# USBINFRTransiever_POWER.net
KiCad netlist of a schematic drawn in Altium Designer
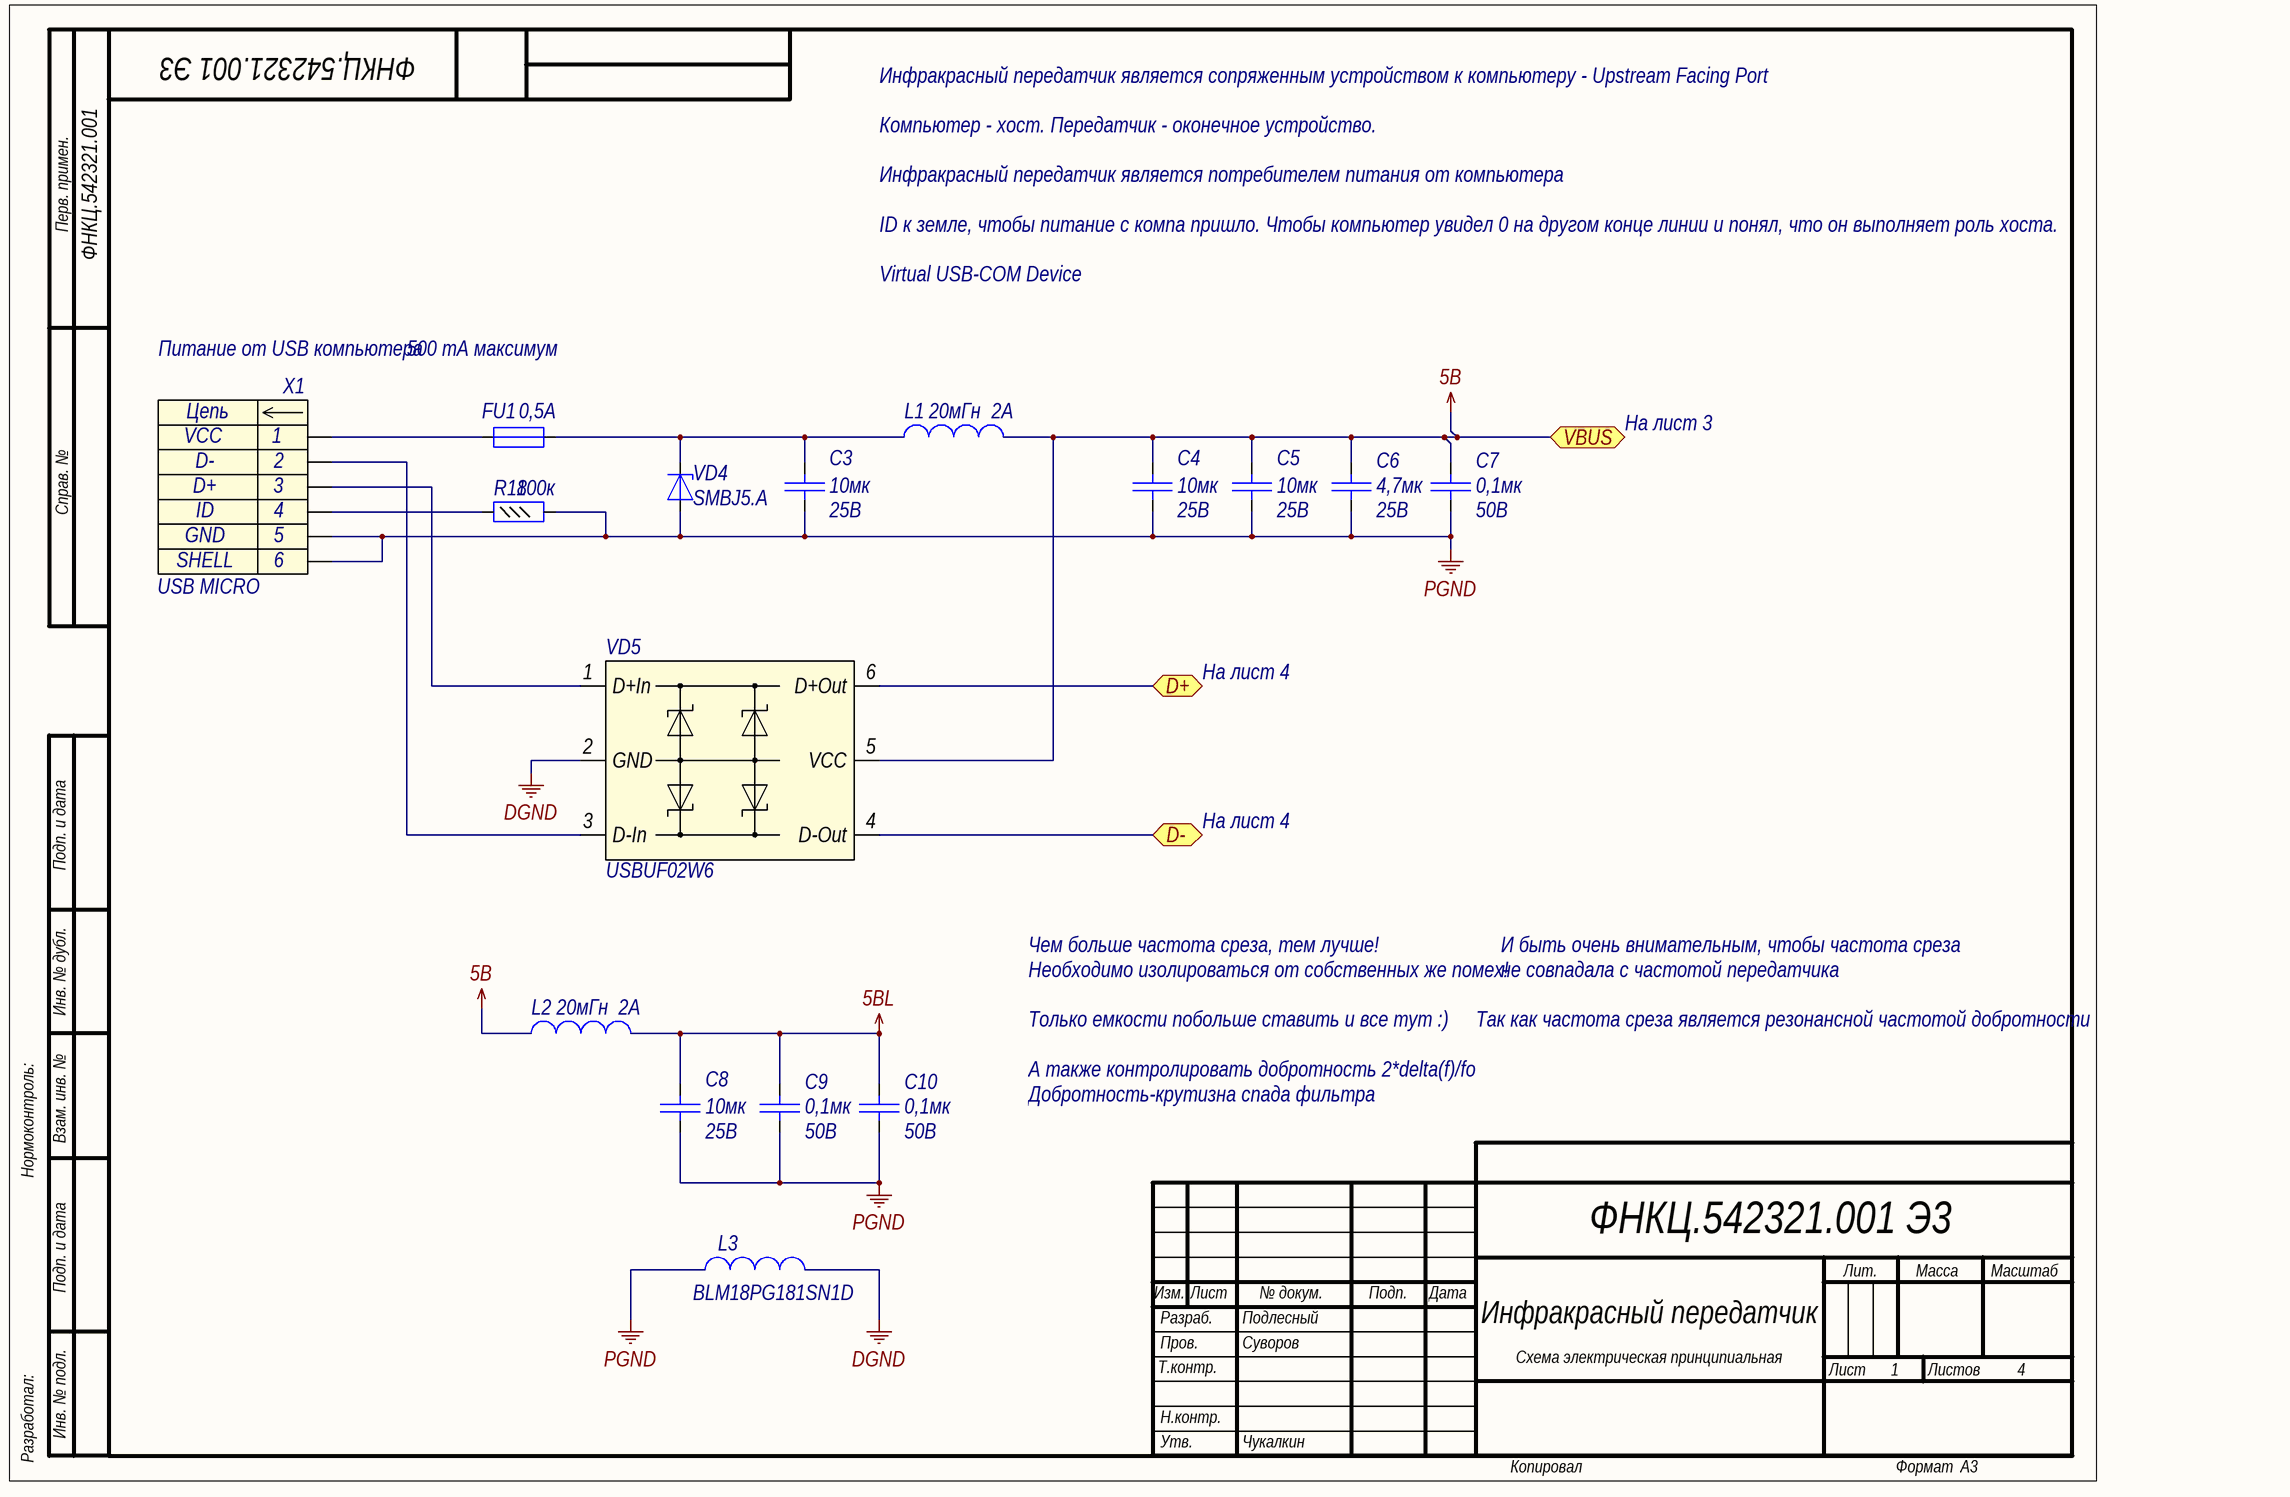
[diagram p0: USBINFRTransiever_POWER.SchDoc]

(export (version "E")
  (design (tool "Eeschema 10.0.6"))
  (components
    (comp (ref "C3")
      (value "10мк")
      (footprint "C1206")
      (description "Конденсатор")
      (fields
        (field (name "VOLTAGE") "25В")
        (field (name "PART NUMBER") "GRM31CR71E106KA12L*")
        (field (name "Comment") "Capacitor")
      )
      (libsource (lib "MOP44") (part "Capacitor"))
    )
    (comp (ref "C4")
      (value "10мк")
      (footprint "C1206")
      (description "Конденсатор")
      (fields
        (field (name "VOLTAGE") "25В")
        (field (name "PART NUMBER") "GRM31CR71E106KA12L*")
        (field (name "Comment") "Capacitor")
      )
      (libsource (lib "MOP44") (part "Capacitor"))
    )
    (comp (ref "C5")
      (value "10мк")
      (footprint "C1206")
      (description "Конденсатор")
      (fields
        (field (name "VOLTAGE") "25В")
        (field (name "PART NUMBER") "GRM31CR71E106KA12L*")
        (field (name "Comment") "Capacitor")
      )
      (libsource (lib "MOP44") (part "Capacitor"))
    )
    (comp (ref "C6")
      (value "4,7мк")
      (footprint "C0805")
      (description "Конденсатор")
      (fields
        (field (name "VOLTAGE") "25B")
        (field (name "PART NUMBER") "GRM21BR61E475KA12L")
        (field (name "Comment") "Capacitor")
      )
      (libsource (lib "MOP44") (part "Capacitor"))
    )
    (comp (ref "C7")
      (value "0,1мк")
      (footprint "C0805")
      (description "Конденсатор")
      (fields
        (field (name "VOLTAGE") "50B")
        (field (name "PART NUMBER") "GRM21BR71H104K**")
        (field (name "Comment") "Capacitor")
      )
      (libsource (lib "MOP44") (part "Capacitor"))
    )
    (comp (ref "C8")
      (value "10мк")
      (footprint "C1206")
      (description "Конденсатор")
      (fields
        (field (name "VOLTAGE") "25В")
        (field (name "PART NUMBER") "GRM31CR71E106KA12L*")
        (field (name "Comment") "Capacitor")
      )
      (libsource (lib "MOP44") (part "Capacitor"))
    )
    (comp (ref "C9")
      (value "0,1мк")
      (footprint "C0805")
      (description "Конденсатор")
      (fields
        (field (name "VOLTAGE") "50B")
        (field (name "PART NUMBER") "GRM21BR71H104K**")
        (field (name "Comment") "Capacitor")
      )
      (libsource (lib "MOP44") (part "Capacitor"))
    )
    (comp (ref "C10")
      (value "0,1мк")
      (footprint "C0805")
      (description "Конденсатор")
      (fields
        (field (name "VOLTAGE") "50B")
        (field (name "PART NUMBER") "GRM21BR71H104K**")
        (field (name "Comment") "Capacitor")
      )
      (libsource (lib "MOP44") (part "Capacitor"))
    )
    (comp (ref "FU1")
      (value "Fuse")
      (footprint "FUSE812")
      (description "Предохранитель")
      (fields (field (name "I HOLD") "0,5A") (field (name "PART NUMBER") "MF-MSMF050"))
      (libsource (lib "MOP44") (part "Fuse"))
    )
    (comp (ref "L1")
      (value "20мГн")
      (footprint "L0805")
      (description "EMI Suppression Filter")
      (fields
        (field (name "RATED CURRENT") "2А")
        (field (name "PART NUMBER") "BLM21PG221SN1D")
        (field (name "Comment") "Inductor")
      )
      (libsource (lib "MOP44") (part "Inductor"))
    )
    (comp (ref "L2")
      (value "20мГн")
      (footprint "L0805")
      (description "EMI Suppression Filter")
      (fields
        (field (name "RATED CURRENT") "2А")
        (field (name "PART NUMBER") "BLM21PG221SN1D")
        (field (name "Comment") "Inductor")
      )
      (libsource (lib "MOP44") (part "Inductor"))
    )
    (comp (ref "L3")
      (value "Inductor")
      (footprint "L0603")
      (description "EMI Suppression Filter")
      (fields (field (name "PART NUMBER") "BLM18PG181SN1D"))
      (libsource (lib "MOP44") (part "Inductor"))
    )
    (comp (ref "R18")
      (value "100к")
      (footprint "R0603")
      (description "Резистор")
      (fields (field (name "PART NUMBER") "RC0603FR-07100KL") (field (name "POWER") "0,062Вт"))
      (libsource (lib "MOP44") (part "Resistor_0,062Вт"))
    )
    (comp (ref "VD4")
      (value "DiodeZener")
      (footprint "SMB")
      (description "Cтабилитрон (лавинный выпрямительный диод) односторонний")
      (fields (field (name "PART NUMBER") "SMBJ5.A"))
      (libsource (lib "MOP44") (part "DiodeZener"))
    )
    (comp (ref "VD5")
      (value "USBUF")
      (footprint "SOT323-6L")
      (description "EMEMI filter and line termination for USB upstream ports")
      (fields (field (name "PART NUMBER") "USBUF02W6"))
      (libsource (lib "MOP44") (part "USBUF"))
    )
    (comp (ref "X1")
      (value "USB MICRO")
      (footprint "47590-0001")
      (libsource (lib "MOP44") (part "USB MICRO"))
    )
  )
  (nets
    (net (code "1") (name "/D+") (class "Default")
      (node (ref "VD5") (pin "6") (pinfunction "D+Out_6") (pintype "passive"))
    )
    (net (code "2") (name "/D-") (class "Default")
      (node (ref "VD5") (pin "4") (pinfunction "D-Out_4") (pintype "passive"))
    )
    (net (code "3") (name "5В") (class "Default")
      (node (ref "C4") (pin "2") (pinfunction "2_2") (pintype "passive"))
      (node (ref "C5") (pin "2") (pinfunction "2_2") (pintype "passive"))
      (node (ref "C6") (pin "2") (pinfunction "2_2") (pintype "passive"))
      (node (ref "C7") (pin "2") (pinfunction "2_2") (pintype "passive"))
      (node (ref "L1") (pin "2") (pinfunction "2_2") (pintype "passive"))
      (node (ref "L2") (pin "1") (pinfunction "1_1") (pintype "passive"))
      (node (ref "VD5") (pin "5") (pinfunction "VCC_5") (pintype "passive"))
    )
    (net (code "4") (name "5ВL") (class "Default")
      (node (ref "C10") (pin "2") (pinfunction "2_2") (pintype "passive"))
      (node (ref "C8") (pin "2") (pinfunction "2_2") (pintype "passive"))
      (node (ref "C9") (pin "2") (pinfunction "2_2") (pintype "passive"))
      (node (ref "L2") (pin "2") (pinfunction "2_2") (pintype "passive"))
    )
    (net (code "5") (name "DGND") (class "Default")
      (node (ref "L3") (pin "2") (pinfunction "2_2") (pintype "passive"))
      (node (ref "VD5") (pin "2") (pinfunction "GND_2") (pintype "passive"))
    )
    (net (code "6") (name "Net-(FU1-Pad1)") (class "Default")
      (node (ref "FU1") (pin "1") (pinfunction "1_1") (pintype "passive"))
      (node (ref "X1") (pin "1") (pinfunction "1_1") (pintype "passive"))
    )
    (net (code "7") (name "Net-(R18-Pad1)") (class "Default")
      (node (ref "R18") (pin "1") (pinfunction "1_1") (pintype "passive"))
      (node (ref "X1") (pin "4") (pinfunction "4_4") (pintype "passive"))
    )
    (net (code "8") (name "Net-(VD4-K)") (class "Default")
      (node (ref "C3") (pin "2") (pinfunction "2_2") (pintype "passive"))
      (node (ref "FU1") (pin "2") (pinfunction "2_2") (pintype "passive"))
      (node (ref "L1") (pin "1") (pinfunction "1_1") (pintype "passive"))
      (node (ref "VD4") (pin "1") (pinfunction "K_1") (pintype "passive"))
    )
    (net (code "9") (name "Net-(VD5-D+In)") (class "Default")
      (node (ref "VD5") (pin "1") (pinfunction "D+In_1") (pintype "passive"))
      (node (ref "X1") (pin "3") (pinfunction "3_3") (pintype "passive"))
    )
    (net (code "10") (name "Net-(VD5-D-In)") (class "Default")
      (node (ref "VD5") (pin "3") (pinfunction "D-In_3") (pintype "passive"))
      (node (ref "X1") (pin "2") (pinfunction "2_2") (pintype "passive"))
    )
    (net (code "11") (name "PGND") (class "Default")
      (node (ref "C10") (pin "1") (pinfunction "1_1") (pintype "passive"))
      (node (ref "C3") (pin "1") (pinfunction "1_1") (pintype "passive"))
      (node (ref "C4") (pin "1") (pinfunction "1_1") (pintype "passive"))
      (node (ref "C5") (pin "1") (pinfunction "1_1") (pintype "passive"))
      (node (ref "C6") (pin "1") (pinfunction "1_1") (pintype "passive"))
      (node (ref "C7") (pin "1") (pinfunction "1_1") (pintype "passive"))
      (node (ref "C8") (pin "1") (pinfunction "1_1") (pintype "passive"))
      (node (ref "C9") (pin "1") (pinfunction "1_1") (pintype "passive"))
      (node (ref "L3") (pin "1") (pinfunction "1_1") (pintype "passive"))
      (node (ref "R18") (pin "2") (pinfunction "2_2") (pintype "passive"))
      (node (ref "VD4") (pin "2") (pinfunction "A_2") (pintype "passive"))
      (node (ref "X1") (pin "5") (pinfunction "5_5") (pintype "passive"))
      (node (ref "X1") (pin "6") (pinfunction "6_6") (pintype "passive"))
    )
  )
)
